# fixed.net
KiCad netlist of a schematic drawn in EAGLE
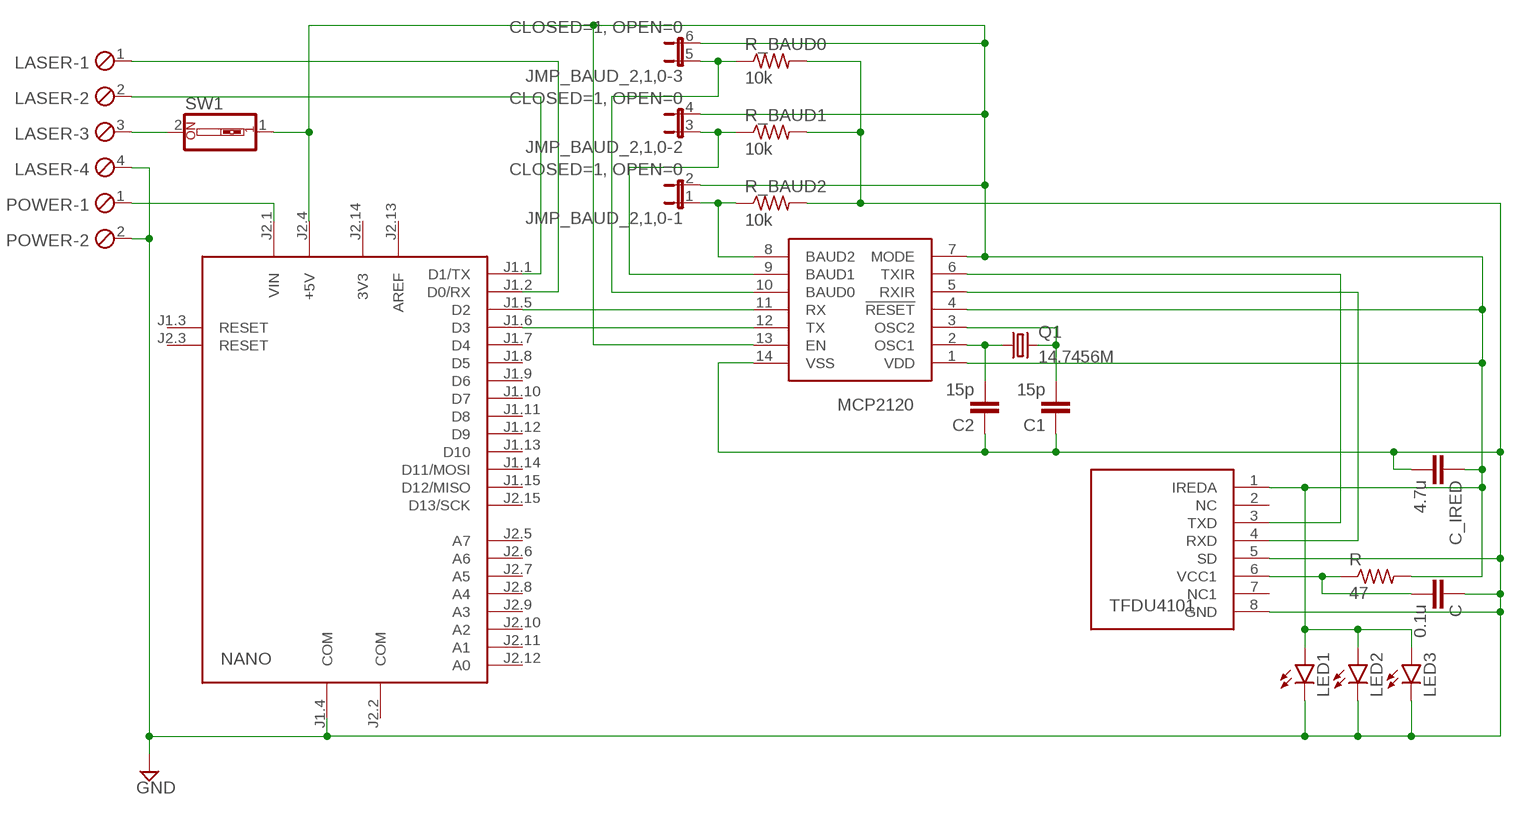
[diagram p0: schematic, sheet 1]

(export (version "E")
  (design (tool "Eeschema 10.0.6"))
  (components
    (comp (ref "C")
      (value "0.1u")
      (footprint "eagle-import:C1206")
      (libsource (lib "eagle-import") (part "C-EUC1206"))
    )
    (comp (ref "C1")
      (value "15p")
      (footprint "eagle-import:C1206")
      (libsource (lib "eagle-import") (part "C-EUC1206"))
    )
    (comp (ref "C2")
      (value "15p")
      (footprint "eagle-import:C1206")
      (libsource (lib "eagle-import") (part "C-EUC1206"))
    )
    (comp (ref "C_IRED")
      (value "4.7u")
      (footprint "eagle-import:C1206")
      (libsource (lib "eagle-import") (part "C-EUC1206"))
    )
    (comp (ref "JMP_BAUD_2,1,0")
      (value "CLOSED=1, OPEN=0")
      (footprint "eagle-import:JP3Q")
      (libsource (lib "eagle-import") (part "JP3QE"))
    )
    (comp (ref "LASER")
      (value "MPT4")
      (footprint "eagle-import:4POL254")
      (libsource (lib "eagle-import") (part "MPT4"))
    )
    (comp (ref "LED1")
      (value "LED5MM")
      (footprint "eagle-import:LED5MM")
      (libsource (lib "eagle-import") (part "LED5MM"))
    )
    (comp (ref "LED2")
      (value "LED5MM")
      (footprint "eagle-import:LED5MM")
      (libsource (lib "eagle-import") (part "LED5MM"))
    )
    (comp (ref "LED3")
      (value "LED5MM")
      (footprint "eagle-import:LED5MM")
      (libsource (lib "eagle-import") (part "LED5MM"))
    )
    (comp (ref "MCP2120")
      (value "MCP2120_SOIC")
      (footprint "eagle-import:SO14")
      (libsource (lib "eagle-import") (part "MCP2120_SOIC"))
    )
    (comp (ref "NANO")
      (value "ARDUINO_NANO2")
      (footprint "eagle-import:ARDUINO_NANO2")
      (libsource (lib "eagle-import") (part "ARDUINO_NANO2"))
    )
    (comp (ref "POWER")
      (value "MPT2")
      (footprint "eagle-import:2POL254")
      (libsource (lib "eagle-import") (part "MPT2"))
    )
    (comp (ref "Q1")
      (value "14.7456M")
      (footprint "eagle-import:TC26V")
      (libsource (lib "eagle-import") (part "CRYSTALTC26V"))
    )
    (comp (ref "R")
      (value "47")
      (footprint "eagle-import:R1206W")
      (libsource (lib "eagle-import") (part "R-US_R1206W"))
    )
    (comp (ref "R_BAUD0")
      (value "10k")
      (footprint "eagle-import:R1206W")
      (libsource (lib "eagle-import") (part "R-US_R1206W"))
    )
    (comp (ref "R_BAUD1")
      (value "10k")
      (footprint "eagle-import:R1206W")
      (libsource (lib "eagle-import") (part "R-US_R1206W"))
    )
    (comp (ref "R_BAUD2")
      (value "10k")
      (footprint "eagle-import:R1206W")
      (libsource (lib "eagle-import") (part "R-US_R1206W"))
    )
    (comp (ref "SW1")
      (value "SW_DIP-1")
      (footprint "eagle-import:EDG-01")
      (libsource (lib "eagle-import") (part "SW_DIP-1"))
    )
    (comp (ref "TFDU4101")
      (value "TFDU4101_TOP")
      (footprint "eagle-import:TFDU4101_TOP")
      (libsource (lib "eagle-import") (part "TFDU4101_TOP"))
    )
  )
  (nets
    (net (code "1") (name "/3V3") (class "Default")
      (node (ref "NANO") (pin "J2.14") (pinfunction "3V3_J2.14") (pintype "power_in"))
    )
    (net (code "2") (name "/AREF") (class "Default")
      (node (ref "NANO") (pin "J2.13") (pinfunction "AREF_J2.13") (pintype "power_in"))
    )
    (net (code "3") (name "/COM") (class "Default")
      (node (ref "NANO") (pin "J2.2") (pinfunction "COM_J2.2") (pintype "power_in"))
    )
    (net (code "4") (name "GND") (class "Default")
      (node (ref "C") (pin "1") (pinfunction "1_1") (pintype "passive"))
      (node (ref "C1") (pin "1") (pinfunction "1_1") (pintype "passive"))
      (node (ref "C2") (pin "1") (pinfunction "1_1") (pintype "passive"))
      (node (ref "C_IRED") (pin "2") (pinfunction "2_2") (pintype "passive"))
      (node (ref "LASER") (pin "4") (pinfunction "1_4") (pintype "passive"))
      (node (ref "LED1") (pin "K") (pinfunction "C_K") (pintype "passive"))
      (node (ref "LED2") (pin "K") (pinfunction "C_K") (pintype "passive"))
      (node (ref "LED3") (pin "K") (pinfunction "C_K") (pintype "passive"))
      (node (ref "MCP2120") (pin "14") (pinfunction "VSS_14") (pintype "bidirectional"))
      (node (ref "NANO") (pin "J1.4") (pinfunction "COM_J1.4") (pintype "power_in"))
      (node (ref "POWER") (pin "2") (pinfunction "1_2") (pintype "passive"))
      (node (ref "R_BAUD0") (pin "2") (pinfunction "2_2") (pintype "passive"))
      (node (ref "R_BAUD1") (pin "2") (pinfunction "2_2") (pintype "passive"))
      (node (ref "R_BAUD2") (pin "2") (pinfunction "2_2") (pintype "passive"))
      (node (ref "TFDU4101") (pin "5") (pinfunction "SD_5") (pintype "bidirectional"))
      (node (ref "TFDU4101") (pin "8") (pinfunction "GND_8") (pintype "bidirectional"))
    )
    (net (code "5") (name "Net-(JMP_BAUD_2,1,0B-1)") (class "Default")
      (node (ref "JMP_BAUD_2,1,0") (pin "3") (pinfunction "1_3") (pintype "passive"))
      (node (ref "MCP2120") (pin "9") (pinfunction "BAUD1_9") (pintype "bidirectional"))
      (node (ref "R_BAUD1") (pin "1") (pinfunction "1_1") (pintype "passive"))
    )
    (net (code "6") (name "Net-(JMP_BAUD_2,1,0B-2)") (class "Default")
      (node (ref "C_IRED") (pin "1") (pinfunction "1_1") (pintype "passive"))
      (node (ref "JMP_BAUD_2,1,0") (pin "2") (pinfunction "2_2") (pintype "passive"))
      (node (ref "JMP_BAUD_2,1,0") (pin "4") (pinfunction "2_4") (pintype "passive"))
      (node (ref "JMP_BAUD_2,1,0") (pin "6") (pinfunction "2_6") (pintype "passive"))
      (node (ref "LED1") (pin "A") (pinfunction "A_A") (pintype "passive"))
      (node (ref "LED2") (pin "A") (pinfunction "A_A") (pintype "passive"))
      (node (ref "LED3") (pin "A") (pinfunction "A_A") (pintype "passive"))
      (node (ref "MCP2120") (pin "1") (pinfunction "VDD_1") (pintype "bidirectional"))
      (node (ref "MCP2120") (pin "13") (pinfunction "EN_13") (pintype "bidirectional"))
      (node (ref "MCP2120") (pin "4") (pinfunction "~{RESET}_4") (pintype "bidirectional"))
      (node (ref "MCP2120") (pin "7") (pinfunction "MODE_7") (pintype "bidirectional"))
      (node (ref "NANO") (pin "J2.4") (pinfunction "+5V_J2.4") (pintype "power_in"))
      (node (ref "R") (pin "2") (pinfunction "2_2") (pintype "passive"))
      (node (ref "SW1") (pin "1") (pinfunction "1_1") (pintype "passive"))
      (node (ref "TFDU4101") (pin "1") (pinfunction "IREDA_1") (pintype "bidirectional"))
    )
    (net (code "7") (name "Net-(JMP_BAUD_2,1,0C-1)") (class "Default")
      (node (ref "JMP_BAUD_2,1,0") (pin "5") (pinfunction "1_5") (pintype "passive"))
      (node (ref "MCP2120") (pin "10") (pinfunction "BAUD0_10") (pintype "bidirectional"))
      (node (ref "R_BAUD0") (pin "1") (pinfunction "1_1") (pintype "passive"))
    )
    (net (code "8") (name "Net-(LASERB-1)") (class "Default")
      (node (ref "LASER") (pin "2") (pinfunction "1_2") (pintype "passive"))
      (node (ref "NANO") (pin "J1.1") (pinfunction "D1/TX_J1.1") (pintype "bidirectional"))
    )
    (net (code "9") (name "Net-(LASERC-1)") (class "Default")
      (node (ref "LASER") (pin "3") (pinfunction "1_3") (pintype "passive"))
      (node (ref "SW1") (pin "2") (pinfunction "2_2") (pintype "passive"))
    )
    (net (code "10") (name "Net-(MCP2120-BAUD2)") (class "Default")
      (node (ref "JMP_BAUD_2,1,0") (pin "1") (pinfunction "1_1") (pintype "passive"))
      (node (ref "MCP2120") (pin "8") (pinfunction "BAUD2_8") (pintype "bidirectional"))
      (node (ref "R_BAUD2") (pin "1") (pinfunction "1_1") (pintype "passive"))
    )
    (net (code "11") (name "Net-(MCP2120-OSC1)") (class "Default")
      (node (ref "C2") (pin "2") (pinfunction "2_2") (pintype "passive"))
      (node (ref "MCP2120") (pin "2") (pinfunction "OSC1_2") (pintype "bidirectional"))
      (node (ref "Q1") (pin "1") (pinfunction "1_1") (pintype "passive"))
    )
    (net (code "12") (name "Net-(MCP2120-OSC2)") (class "Default")
      (node (ref "C1") (pin "2") (pinfunction "2_2") (pintype "passive"))
      (node (ref "MCP2120") (pin "3") (pinfunction "OSC2_3") (pintype "bidirectional"))
      (node (ref "Q1") (pin "2") (pinfunction "2_2") (pintype "passive"))
    )
    (net (code "13") (name "Net-(MCP2120-RX)") (class "Default")
      (node (ref "MCP2120") (pin "11") (pinfunction "RX_11") (pintype "bidirectional"))
      (node (ref "NANO") (pin "J1.5") (pinfunction "D2_J1.5") (pintype "bidirectional"))
    )
    (net (code "14") (name "Net-(MCP2120-RXIR)") (class "Default")
      (node (ref "MCP2120") (pin "5") (pinfunction "RXIR_5") (pintype "bidirectional"))
      (node (ref "TFDU4101") (pin "4") (pinfunction "RXD_4") (pintype "bidirectional"))
    )
    (net (code "15") (name "Net-(MCP2120-TX)") (class "Default")
      (node (ref "MCP2120") (pin "12") (pinfunction "TX_12") (pintype "bidirectional"))
      (node (ref "NANO") (pin "J1.6") (pinfunction "D3_J1.6") (pintype "bidirectional"))
    )
    (net (code "16") (name "Net-(MCP2120-TXIR)") (class "Default")
      (node (ref "MCP2120") (pin "6") (pinfunction "TXIR_6") (pintype "bidirectional"))
      (node (ref "TFDU4101") (pin "3") (pinfunction "TXD_3") (pintype "bidirectional"))
    )
    (net (code "17") (name "Net-(NANO-D0{slash}RX)") (class "Default")
      (node (ref "LASER") (pin "1") (pinfunction "1_1") (pintype "passive"))
      (node (ref "NANO") (pin "J1.2") (pinfunction "D0/RX_J1.2") (pintype "bidirectional"))
    )
    (net (code "18") (name "Net-(NANO-VIN)") (class "Default")
      (node (ref "NANO") (pin "J2.1") (pinfunction "VIN_J2.1") (pintype "power_in"))
      (node (ref "POWER") (pin "1") (pinfunction "1_1") (pintype "passive"))
    )
    (net (code "19") (name "Net-(TFDU4101-VCC1)") (class "Default")
      (node (ref "C") (pin "2") (pinfunction "2_2") (pintype "passive"))
      (node (ref "R") (pin "1") (pinfunction "1_1") (pintype "passive"))
      (node (ref "TFDU4101") (pin "6") (pinfunction "VCC1_6") (pintype "bidirectional"))
    )
    (net (code "20") (name "unconnected-(NANO-A0-PadJ2.12)") (class "Default")
      (node (ref "NANO") (pin "J2.12") (pinfunction "A0_J2.12") (pintype "bidirectional"))
    )
    (net (code "21") (name "unconnected-(NANO-A1-PadJ2.11)") (class "Default")
      (node (ref "NANO") (pin "J2.11") (pinfunction "A1_J2.11") (pintype "bidirectional"))
    )
    (net (code "22") (name "unconnected-(NANO-A2-PadJ2.10)") (class "Default")
      (node (ref "NANO") (pin "J2.10") (pinfunction "A2_J2.10") (pintype "bidirectional"))
    )
    (net (code "23") (name "unconnected-(NANO-A3-PadJ2.9)") (class "Default")
      (node (ref "NANO") (pin "J2.9") (pinfunction "A3_J2.9") (pintype "bidirectional"))
    )
    (net (code "24") (name "unconnected-(NANO-A4-PadJ2.8)") (class "Default")
      (node (ref "NANO") (pin "J2.8") (pinfunction "A4_J2.8") (pintype "bidirectional"))
    )
    (net (code "25") (name "unconnected-(NANO-A5-PadJ2.7)") (class "Default")
      (node (ref "NANO") (pin "J2.7") (pinfunction "A5_J2.7") (pintype "bidirectional"))
    )
    (net (code "26") (name "unconnected-(NANO-A6-PadJ2.6)") (class "Default")
      (node (ref "NANO") (pin "J2.6") (pinfunction "A6_J2.6") (pintype "bidirectional"))
    )
    (net (code "27") (name "unconnected-(NANO-A7-PadJ2.5)") (class "Default")
      (node (ref "NANO") (pin "J2.5") (pinfunction "A7_J2.5") (pintype "bidirectional"))
    )
    (net (code "28") (name "unconnected-(NANO-D4-PadJ1.7)") (class "Default")
      (node (ref "NANO") (pin "J1.7") (pinfunction "D4_J1.7") (pintype "bidirectional"))
    )
    (net (code "29") (name "unconnected-(NANO-D5-PadJ1.8)") (class "Default")
      (node (ref "NANO") (pin "J1.8") (pinfunction "D5_J1.8") (pintype "bidirectional"))
    )
    (net (code "30") (name "unconnected-(NANO-D6-PadJ1.9)") (class "Default")
      (node (ref "NANO") (pin "J1.9") (pinfunction "D6_J1.9") (pintype "bidirectional"))
    )
    (net (code "31") (name "unconnected-(NANO-D7-PadJ1.10)") (class "Default")
      (node (ref "NANO") (pin "J1.10") (pinfunction "D7_J1.10") (pintype "bidirectional"))
    )
    (net (code "32") (name "unconnected-(NANO-D8-PadJ1.11)") (class "Default")
      (node (ref "NANO") (pin "J1.11") (pinfunction "D8_J1.11") (pintype "bidirectional"))
    )
    (net (code "33") (name "unconnected-(NANO-D9-PadJ1.12)") (class "Default")
      (node (ref "NANO") (pin "J1.12") (pinfunction "D9_J1.12") (pintype "bidirectional"))
    )
    (net (code "34") (name "unconnected-(NANO-D10-PadJ1.13)") (class "Default")
      (node (ref "NANO") (pin "J1.13") (pinfunction "D10_J1.13") (pintype "bidirectional"))
    )
    (net (code "35") (name "unconnected-(NANO-D11{slash}MOSI-PadJ1.14)") (class "Default")
      (node (ref "NANO") (pin "J1.14") (pinfunction "D11/MOSI_J1.14") (pintype "bidirectional"))
    )
    (net (code "36") (name "unconnected-(NANO-D12{slash}MISO-PadJ1.15)") (class "Default")
      (node (ref "NANO") (pin "J1.15") (pinfunction "D12/MISO_J1.15") (pintype "bidirectional"))
    )
    (net (code "37") (name "unconnected-(NANO-D13{slash}SCK-PadJ2.15)") (class "Default")
      (node (ref "NANO") (pin "J2.15") (pinfunction "D13/SCK_J2.15") (pintype "bidirectional"))
    )
    (net (code "38") (name "unconnected-(NANO-RESET-PadJ1.3)") (class "Default")
      (node (ref "NANO") (pin "J1.3") (pinfunction "RESET_J1.3") (pintype "bidirectional"))
    )
    (net (code "39") (name "unconnected-(NANO-RESET-PadJ2.3)") (class "Default")
      (node (ref "NANO") (pin "J2.3") (pinfunction "RESET_J2.3") (pintype "bidirectional"))
    )
    (net (code "40") (name "unconnected-(TFDU4101-NC-Pad2)") (class "Default")
      (node (ref "TFDU4101") (pin "2") (pinfunction "NC_2") (pintype "bidirectional"))
    )
    (net (code "41") (name "unconnected-(TFDU4101-NC1-Pad7)") (class "Default")
      (node (ref "TFDU4101") (pin "7") (pinfunction "NC1_7") (pintype "bidirectional"))
    )
  )
)
